# term_clock.net
KiCad netlist of a schematic drawn in EAGLE
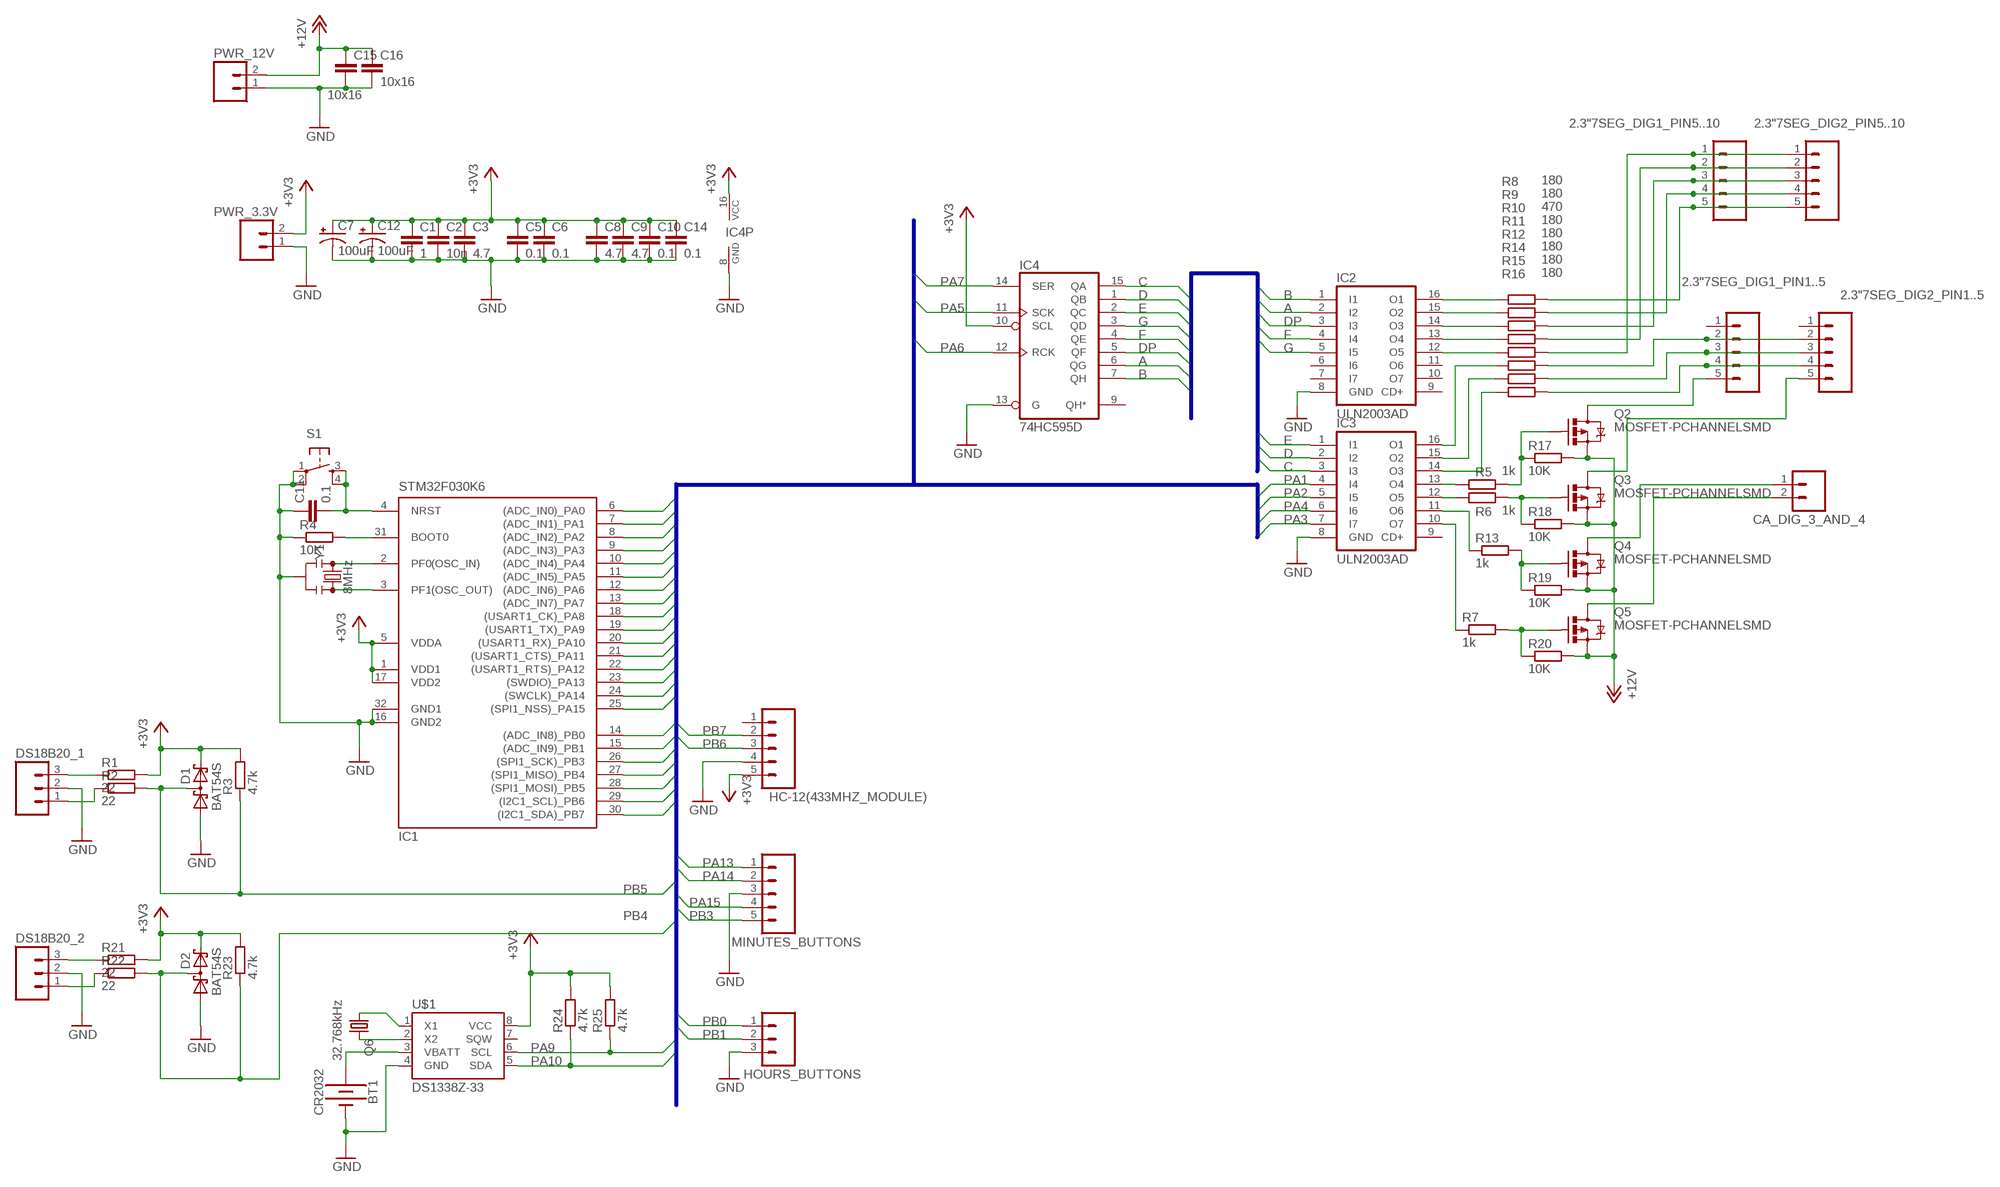
[diagram p0: schematic, sheet 1]

(export (version "E")
  (design (tool "Eeschema 10.0.6"))
  (components
    (comp (ref "2.3\"7SEG_DIG1_PIN1..5")
      (value "M05")
      (footprint "eagle-import:05P")
      (libsource (lib "eagle-import") (part "M05"))
    )
    (comp (ref "2.3\"7SEG_DIG1_PIN5..10")
      (value "M05")
      (footprint "eagle-import:05P")
      (libsource (lib "eagle-import") (part "M05"))
    )
    (comp (ref "2.3\"7SEG_DIG2_PIN1..5")
      (value "M05")
      (footprint "eagle-import:05P")
      (libsource (lib "eagle-import") (part "M05"))
    )
    (comp (ref "2.3\"7SEG_DIG2_PIN5..10")
      (value "M05")
      (footprint "eagle-import:05P")
      (libsource (lib "eagle-import") (part "M05"))
    )
    (comp (ref "BT1")
      (value "CR2032")
      (footprint "eagle-import:BATTCOM_20MM_PTH")
      (libsource (lib "eagle-import") (part "BATTERY-20MM_PTH"))
    )
    (comp (ref "C1")
      (value "1")
      (footprint "eagle-import:C0805")
      (libsource (lib "eagle-import") (part "C-EUC0805"))
    )
    (comp (ref "C2")
      (value "10n")
      (footprint "eagle-import:C0805")
      (libsource (lib "eagle-import") (part "C-EUC0805"))
    )
    (comp (ref "C3")
      (value "4.7")
      (footprint "eagle-import:C0805")
      (libsource (lib "eagle-import") (part "C-EUC0805"))
    )
    (comp (ref "C5")
      (value "0.1")
      (footprint "eagle-import:C0805")
      (libsource (lib "eagle-import") (part "C-EUC0805"))
    )
    (comp (ref "C6")
      (value "0.1")
      (footprint "eagle-import:C0805")
      (libsource (lib "eagle-import") (part "C-EUC0805"))
    )
    (comp (ref "C7")
      (value "100uF")
      (footprint "eagle-import:EIA7343")
      (libsource (lib "eagle-import") (part "100UF-POLAR-EIA7343-16V-10%(TANT)"))
    )
    (comp (ref "C8")
      (value "4.7")
      (footprint "eagle-import:C0805")
      (libsource (lib "eagle-import") (part "C-EUC0805"))
    )
    (comp (ref "C9")
      (value "4.7")
      (footprint "eagle-import:C0805")
      (libsource (lib "eagle-import") (part "C-EUC0805"))
    )
    (comp (ref "C10")
      (value "0.1")
      (footprint "eagle-import:C0805")
      (libsource (lib "eagle-import") (part "C-EUC0805"))
    )
    (comp (ref "C11")
      (value "0.1")
      (footprint "eagle-import:C0805")
      (libsource (lib "eagle-import") (part "C-EUC0805"))
    )
    (comp (ref "C12")
      (value "100uF")
      (footprint "eagle-import:EIA7343")
      (libsource (lib "eagle-import") (part "100UF-POLAR-EIA7343-16V-10%(TANT)"))
    )
    (comp (ref "C14")
      (value "0.1")
      (footprint "eagle-import:C0805")
      (libsource (lib "eagle-import") (part "C-EUC0805"))
    )
    (comp (ref "C15")
      (value "10x16")
      (footprint "eagle-import:C1206")
      (libsource (lib "eagle-import") (part "C-EUC1206"))
    )
    (comp (ref "C16")
      (value "10x16")
      (footprint "eagle-import:C1206")
      (libsource (lib "eagle-import") (part "C-EUC1206"))
    )
    (comp (ref "CA_DIG_3_AND_4")
      (value "M02")
      (footprint "eagle-import:02P")
      (libsource (lib "eagle-import") (part "M02"))
    )
    (comp (ref "D1")
      (value "BAT54S")
      (footprint "eagle-import:SOT23")
      (libsource (lib "eagle-import") (part "BAT54S"))
    )
    (comp (ref "D2")
      (value "BAT54S")
      (footprint "eagle-import:SOT23")
      (libsource (lib "eagle-import") (part "BAT54S"))
    )
    (comp (ref "DS18B20_1")
      (value "M03")
      (footprint "eagle-import:03P")
      (libsource (lib "eagle-import") (part "M03"))
    )
    (comp (ref "DS18B20_2")
      (value "M03")
      (footprint "eagle-import:03P")
      (libsource (lib "eagle-import") (part "M03"))
    )
    (comp (ref "HC-12(433MHZ_MODULE)")
      (value "M05")
      (footprint "eagle-import:05P")
      (libsource (lib "eagle-import") (part "M05"))
    )
    (comp (ref "HOURS_BUTTONS")
      (value "M03")
      (footprint "eagle-import:03P")
      (libsource (lib "eagle-import") (part "M03"))
    )
    (comp (ref "IC1")
      (value "STM32F030K6")
      (footprint "eagle-import:TQFP32-08")
      (libsource (lib "eagle-import") (part "STM32F030K6"))
    )
    (comp (ref "IC2")
      (value "ULN2003AD")
      (footprint "eagle-import:SO16")
      (libsource (lib "eagle-import") (part "ULN2003AD"))
    )
    (comp (ref "IC3")
      (value "ULN2003AD")
      (footprint "eagle-import:SO16")
      (libsource (lib "eagle-import") (part "ULN2003AD"))
    )
    (comp (ref "IC4")
      (value "74HC595D")
      (footprint "eagle-import:SO16")
      (libsource (lib "eagle-import") (part "74595DHC"))
    )
    (comp (ref "MINUTES_BUTTONS")
      (value "M05")
      (footprint "eagle-import:05P")
      (libsource (lib "eagle-import") (part "M05"))
    )
    (comp (ref "PWR_3.3V")
      (value "M02")
      (footprint "eagle-import:02P")
      (libsource (lib "eagle-import") (part "M02"))
    )
    (comp (ref "PWR_12V")
      (value "M02")
      (footprint "eagle-import:02P")
      (libsource (lib "eagle-import") (part "M02"))
    )
    (comp (ref "Q2")
      (value "MOSFET-PCHANNELSMD")
      (footprint "eagle-import:SOT23-3")
      (libsource (lib "eagle-import") (part "MOSFET-PCHANNELSMD"))
    )
    (comp (ref "Q3")
      (value "MOSFET-PCHANNELSMD")
      (footprint "eagle-import:SOT23-3")
      (libsource (lib "eagle-import") (part "MOSFET-PCHANNELSMD"))
    )
    (comp (ref "Q4")
      (value "MOSFET-PCHANNELSMD")
      (footprint "eagle-import:SOT23-3")
      (libsource (lib "eagle-import") (part "MOSFET-PCHANNELSMD"))
    )
    (comp (ref "Q5")
      (value "MOSFET-PCHANNELSMD")
      (footprint "eagle-import:SOT23-3")
      (libsource (lib "eagle-import") (part "MOSFET-PCHANNELSMD"))
    )
    (comp (ref "Q6")
      (value "32.768kHz")
      (footprint "eagle-import:TC38H")
      (libsource (lib "eagle-import") (part "CRYSTALTC38H"))
    )
    (comp (ref "R1")
      (value "22")
      (footprint "eagle-import:R0805")
      (libsource (lib "eagle-import") (part "R-EU_R0805"))
    )
    (comp (ref "R2")
      (value "22")
      (footprint "eagle-import:R0805")
      (libsource (lib "eagle-import") (part "R-EU_R0805"))
    )
    (comp (ref "R3")
      (value "4.7k")
      (footprint "eagle-import:R0805")
      (libsource (lib "eagle-import") (part "R-EU_R0805"))
    )
    (comp (ref "R4")
      (value "10K")
      (footprint "eagle-import:R0805")
      (libsource (lib "eagle-import") (part "R-EU_R0805"))
    )
    (comp (ref "R5")
      (value "1k")
      (footprint "eagle-import:R0603")
      (libsource (lib "eagle-import") (part "R-EU_R0603"))
    )
    (comp (ref "R6")
      (value "1k")
      (footprint "eagle-import:R0603")
      (libsource (lib "eagle-import") (part "R-EU_R0603"))
    )
    (comp (ref "R7")
      (value "1k")
      (footprint "eagle-import:R0603")
      (libsource (lib "eagle-import") (part "R-EU_R0603"))
    )
    (comp (ref "R8")
      (value "180")
      (footprint "eagle-import:R1206")
      (libsource (lib "eagle-import") (part "R-EU_R1206"))
    )
    (comp (ref "R9")
      (value "180")
      (footprint "eagle-import:R1206")
      (libsource (lib "eagle-import") (part "R-EU_R1206"))
    )
    (comp (ref "R10")
      (value "470")
      (footprint "eagle-import:R1206")
      (libsource (lib "eagle-import") (part "R-EU_R1206"))
    )
    (comp (ref "R11")
      (value "180")
      (footprint "eagle-import:R1206")
      (libsource (lib "eagle-import") (part "R-EU_R1206"))
    )
    (comp (ref "R12")
      (value "180")
      (footprint "eagle-import:R1206")
      (libsource (lib "eagle-import") (part "R-EU_R1206"))
    )
    (comp (ref "R13")
      (value "1k")
      (footprint "eagle-import:R0603")
      (libsource (lib "eagle-import") (part "R-EU_R0603"))
    )
    (comp (ref "R14")
      (value "180")
      (footprint "eagle-import:R1206")
      (libsource (lib "eagle-import") (part "R-EU_R1206"))
    )
    (comp (ref "R15")
      (value "180")
      (footprint "eagle-import:R1206")
      (libsource (lib "eagle-import") (part "R-EU_R1206"))
    )
    (comp (ref "R16")
      (value "180")
      (footprint "eagle-import:R1206")
      (libsource (lib "eagle-import") (part "R-EU_R1206"))
    )
    (comp (ref "R17")
      (value "10K")
      (footprint "eagle-import:R0603")
      (libsource (lib "eagle-import") (part "R-EU_R0603"))
    )
    (comp (ref "R18")
      (value "10K")
      (footprint "eagle-import:R0603")
      (libsource (lib "eagle-import") (part "R-EU_R0603"))
    )
    (comp (ref "R19")
      (value "10K")
      (footprint "eagle-import:R0603")
      (libsource (lib "eagle-import") (part "R-EU_R0603"))
    )
    (comp (ref "R20")
      (value "10K")
      (footprint "eagle-import:R0603")
      (libsource (lib "eagle-import") (part "R-EU_R0603"))
    )
    (comp (ref "R21")
      (value "22")
      (footprint "eagle-import:R0805")
      (libsource (lib "eagle-import") (part "R-EU_R0805"))
    )
    (comp (ref "R22")
      (value "22")
      (footprint "eagle-import:R0805")
      (libsource (lib "eagle-import") (part "R-EU_R0805"))
    )
    (comp (ref "R23")
      (value "4.7k")
      (footprint "eagle-import:R0805")
      (libsource (lib "eagle-import") (part "R-EU_R0805"))
    )
    (comp (ref "R24")
      (value "4.7k")
      (footprint "eagle-import:R0805")
      (libsource (lib "eagle-import") (part "R-EU_R0805"))
    )
    (comp (ref "R25")
      (value "4.7k")
      (footprint "eagle-import:R0805")
      (libsource (lib "eagle-import") (part "R-EU_R0805"))
    )
    (comp (ref "S1")
      (value "TAC_SWITCHSMD")
      (footprint "eagle-import:TACTILE_SWITCH_SMD")
      (libsource (lib "eagle-import") (part "TAC_SWITCHSMD"))
    )
    (comp (ref "U$1")
      (value "DS1338Z-33")
      (footprint "eagle-import:SO08")
      (libsource (lib "eagle-import") (part "DS1307SO8"))
    )
    (comp (ref "Y1")
      (value "8MHz")
      (footprint "eagle-import:RESONATOR-SMD-3.2X1.3")
      (libsource (lib "eagle-import") (part "RESONATOR-8MHZSMD_3.2X1.3"))
    )
  )
  (nets
    (net (code "1") (name "+3V3") (class "Default")
      (node (ref "C1") (pin "1") (pinfunction "1_1") (pintype "passive"))
      (node (ref "C10") (pin "1") (pinfunction "1_1") (pintype "passive"))
      (node (ref "C12") (pin "A") (pinfunction "+_A") (pintype "passive"))
      (node (ref "C14") (pin "1") (pinfunction "1_1") (pintype "passive"))
      (node (ref "C2") (pin "1") (pinfunction "1_1") (pintype "passive"))
      (node (ref "C3") (pin "1") (pinfunction "1_1") (pintype "passive"))
      (node (ref "C5") (pin "1") (pinfunction "1_1") (pintype "passive"))
      (node (ref "C6") (pin "1") (pinfunction "1_1") (pintype "passive"))
      (node (ref "C7") (pin "A") (pinfunction "+_A") (pintype "passive"))
      (node (ref "C8") (pin "1") (pinfunction "1_1") (pintype "passive"))
      (node (ref "C9") (pin "1") (pinfunction "1_1") (pintype "passive"))
      (node (ref "D1") (pin "2") (pinfunction "C2_2") (pintype "passive"))
      (node (ref "D2") (pin "2") (pinfunction "C2_2") (pintype "passive"))
      (node (ref "HC-12(433MHZ_MODULE)") (pin "5") (pinfunction "5_5") (pintype "passive"))
      (node (ref "IC1") (pin "1") (pinfunction "VDD1_1") (pintype "power_in"))
      (node (ref "IC1") (pin "17") (pinfunction "VDD2_17") (pintype "power_in"))
      (node (ref "IC1") (pin "5") (pinfunction "VDDA_5") (pintype "power_in"))
      (node (ref "IC4") (pin "10") (pinfunction "SCL_10") (pintype "input"))
      (node (ref "IC4") (pin "16") (pinfunction "VCC_16") (pintype "power_in"))
      (node (ref "PWR_3.3V") (pin "2") (pinfunction "2_2") (pintype "passive"))
      (node (ref "R1") (pin "2") (pinfunction "2_2") (pintype "passive"))
      (node (ref "R21") (pin "2") (pinfunction "2_2") (pintype "passive"))
      (node (ref "R23") (pin "2") (pinfunction "2_2") (pintype "passive"))
      (node (ref "R24") (pin "2") (pinfunction "2_2") (pintype "passive"))
      (node (ref "R25") (pin "2") (pinfunction "2_2") (pintype "passive"))
      (node (ref "R3") (pin "2") (pinfunction "2_2") (pintype "passive"))
      (node (ref "U$1") (pin "8") (pinfunction "VCC_8") (pintype "bidirectional"))
    )
    (net (code "2") (name "+12V") (class "Default")
      (node (ref "C15") (pin "1") (pinfunction "1_1") (pintype "passive"))
      (node (ref "C16") (pin "1") (pinfunction "1_1") (pintype "passive"))
      (node (ref "PWR_12V") (pin "2") (pinfunction "2_2") (pintype "passive"))
      (node (ref "Q2") (pin "2") (pinfunction "S_2") (pintype "passive"))
      (node (ref "Q3") (pin "2") (pinfunction "S_2") (pintype "passive"))
      (node (ref "Q4") (pin "2") (pinfunction "S_2") (pintype "passive"))
      (node (ref "Q5") (pin "2") (pinfunction "S_2") (pintype "passive"))
      (node (ref "R17") (pin "2") (pinfunction "2_2") (pintype "passive"))
      (node (ref "R18") (pin "2") (pinfunction "2_2") (pintype "passive"))
      (node (ref "R19") (pin "2") (pinfunction "2_2") (pintype "passive"))
      (node (ref "R20") (pin "2") (pinfunction "2_2") (pintype "passive"))
    )
    (net (code "3") (name "/A") (class "Default")
      (node (ref "IC2") (pin "2") (pinfunction "I2_2") (pintype "input"))
      (node (ref "IC4") (pin "6") (pinfunction "QG_6") (pintype "tri_state"))
    )
    (net (code "4") (name "/B") (class "Default")
      (node (ref "IC2") (pin "1") (pinfunction "I1_1") (pintype "input"))
      (node (ref "IC4") (pin "7") (pinfunction "QH_7") (pintype "tri_state"))
    )
    (net (code "5") (name "/C") (class "Default")
      (node (ref "IC3") (pin "3") (pinfunction "I3_3") (pintype "input"))
      (node (ref "IC4") (pin "15") (pinfunction "QA_15") (pintype "tri_state"))
    )
    (net (code "6") (name "/D") (class "Default")
      (node (ref "IC3") (pin "2") (pinfunction "I2_2") (pintype "input"))
      (node (ref "IC4") (pin "1") (pinfunction "QB_1") (pintype "tri_state"))
    )
    (net (code "7") (name "/DP") (class "Default")
      (node (ref "IC2") (pin "3") (pinfunction "I3_3") (pintype "input"))
      (node (ref "IC4") (pin "5") (pinfunction "QF_5") (pintype "tri_state"))
    )
    (net (code "8") (name "/E") (class "Default")
      (node (ref "IC3") (pin "1") (pinfunction "I1_1") (pintype "input"))
      (node (ref "IC4") (pin "2") (pinfunction "QC_2") (pintype "tri_state"))
    )
    (net (code "9") (name "/F") (class "Default")
      (node (ref "IC2") (pin "4") (pinfunction "I4_4") (pintype "input"))
      (node (ref "IC4") (pin "4") (pinfunction "QE_4") (pintype "tri_state"))
    )
    (net (code "10") (name "/G") (class "Default")
      (node (ref "IC2") (pin "5") (pinfunction "I5_5") (pintype "input"))
      (node (ref "IC4") (pin "3") (pinfunction "QD_3") (pintype "tri_state"))
    )
    (net (code "11") (name "/PA1") (class "Default")
      (node (ref "IC1") (pin "7") (pinfunction "(ADC_IN1)_PA1_7") (pintype "bidirectional"))
      (node (ref "IC3") (pin "4") (pinfunction "I4_4") (pintype "input"))
    )
    (net (code "12") (name "/PA2") (class "Default")
      (node (ref "IC1") (pin "8") (pinfunction "(ADC_IN2)_PA2_8") (pintype "bidirectional"))
      (node (ref "IC3") (pin "5") (pinfunction "I5_5") (pintype "input"))
    )
    (net (code "13") (name "/PA3") (class "Default")
      (node (ref "IC1") (pin "9") (pinfunction "(ADC_IN3)_PA3_9") (pintype "bidirectional"))
      (node (ref "IC3") (pin "7") (pinfunction "I7_7") (pintype "input"))
    )
    (net (code "14") (name "/PA4") (class "Default")
      (node (ref "IC1") (pin "10") (pinfunction "(ADC_IN4)_PA4_10") (pintype "bidirectional"))
      (node (ref "IC3") (pin "6") (pinfunction "I6_6") (pintype "input"))
    )
    (net (code "15") (name "/PA5") (class "Default")
      (node (ref "IC1") (pin "11") (pinfunction "(ADC_IN5)_PA5_11") (pintype "bidirectional"))
      (node (ref "IC4") (pin "11") (pinfunction "SCK_11") (pintype "input"))
    )
    (net (code "16") (name "/PA6") (class "Default")
      (node (ref "IC1") (pin "12") (pinfunction "(ADC_IN6)_PA6_12") (pintype "bidirectional"))
      (node (ref "IC4") (pin "12") (pinfunction "RCK_12") (pintype "input"))
    )
    (net (code "17") (name "/PA7") (class "Default")
      (node (ref "IC1") (pin "13") (pinfunction "(ADC_IN7)_PA7_13") (pintype "bidirectional"))
      (node (ref "IC4") (pin "14") (pinfunction "SER_14") (pintype "input"))
    )
    (net (code "18") (name "/PA9") (class "Default")
      (node (ref "IC1") (pin "19") (pinfunction "(USART1_TX)_PA9_19") (pintype "bidirectional"))
      (node (ref "R25") (pin "1") (pinfunction "1_1") (pintype "passive"))
      (node (ref "U$1") (pin "6") (pinfunction "SCL_6") (pintype "bidirectional"))
    )
    (net (code "19") (name "/PA10") (class "Default")
      (node (ref "IC1") (pin "20") (pinfunction "(USART1_RX)_PA10_20") (pintype "bidirectional"))
      (node (ref "R24") (pin "1") (pinfunction "1_1") (pintype "passive"))
      (node (ref "U$1") (pin "5") (pinfunction "SDA_5") (pintype "bidirectional"))
    )
    (net (code "20") (name "/PA13") (class "Default")
      (node (ref "IC1") (pin "23") (pinfunction "(SWDIO)_PA13_23") (pintype "bidirectional"))
      (node (ref "MINUTES_BUTTONS") (pin "1") (pinfunction "1_1") (pintype "passive"))
    )
    (net (code "21") (name "/PA14") (class "Default")
      (node (ref "IC1") (pin "24") (pinfunction "(SWCLK)_PA14_24") (pintype "bidirectional"))
      (node (ref "MINUTES_BUTTONS") (pin "2") (pinfunction "2_2") (pintype "passive"))
    )
    (net (code "22") (name "/PA15") (class "Default")
      (node (ref "IC1") (pin "25") (pinfunction "(SPI1_NSS)_PA15_25") (pintype "bidirectional"))
      (node (ref "MINUTES_BUTTONS") (pin "4") (pinfunction "4_4") (pintype "passive"))
    )
    (net (code "23") (name "/PB0") (class "Default")
      (node (ref "HOURS_BUTTONS") (pin "1") (pinfunction "1_1") (pintype "passive"))
      (node (ref "IC1") (pin "14") (pinfunction "(ADC_IN8)_PB0_14") (pintype "bidirectional"))
    )
    (net (code "24") (name "/PB1") (class "Default")
      (node (ref "HOURS_BUTTONS") (pin "2") (pinfunction "2_2") (pintype "passive"))
      (node (ref "IC1") (pin "15") (pinfunction "(ADC_IN9)_PB1_15") (pintype "bidirectional"))
    )
    (net (code "25") (name "/PB3") (class "Default")
      (node (ref "IC1") (pin "26") (pinfunction "(SPI1_SCK)_PB3_26") (pintype "bidirectional"))
      (node (ref "MINUTES_BUTTONS") (pin "5") (pinfunction "5_5") (pintype "passive"))
    )
    (net (code "26") (name "/PB4") (class "Default")
      (node (ref "D2") (pin "3") (pinfunction "C1A2_3") (pintype "passive"))
      (node (ref "IC1") (pin "27") (pinfunction "(SPI1_MISO)_PB4_27") (pintype "bidirectional"))
      (node (ref "R22") (pin "2") (pinfunction "2_2") (pintype "passive"))
      (node (ref "R23") (pin "1") (pinfunction "1_1") (pintype "passive"))
    )
    (net (code "27") (name "/PB5") (class "Default")
      (node (ref "D1") (pin "3") (pinfunction "C1A2_3") (pintype "passive"))
      (node (ref "IC1") (pin "28") (pinfunction "(SPI1_MOSI)_PB5_28") (pintype "bidirectional"))
      (node (ref "R2") (pin "2") (pinfunction "2_2") (pintype "passive"))
      (node (ref "R3") (pin "1") (pinfunction "1_1") (pintype "passive"))
    )
    (net (code "28") (name "/PB6") (class "Default")
      (node (ref "HC-12(433MHZ_MODULE)") (pin "3") (pinfunction "3_3") (pintype "passive"))
      (node (ref "IC1") (pin "29") (pinfunction "(I2C1_SCL)_PB6_29") (pintype "bidirectional"))
    )
    (net (code "29") (name "/PB7") (class "Default")
      (node (ref "HC-12(433MHZ_MODULE)") (pin "2") (pinfunction "2_2") (pintype "passive"))
      (node (ref "IC1") (pin "30") (pinfunction "(I2C1_SDA)_PB7_30") (pintype "bidirectional"))
    )
    (net (code "30") (name "GND") (class "Default")
      (node (ref "BT1") (pin "2") (pinfunction "-_2") (pintype "power_in"))
      (node (ref "C1") (pin "2") (pinfunction "2_2") (pintype "passive"))
      (node (ref "C10") (pin "2") (pinfunction "2_2") (pintype "passive"))
      (node (ref "C11") (pin "1") (pinfunction "1_1") (pintype "passive"))
      (node (ref "C12") (pin "C") (pinfunction "-_C") (pintype "passive"))
      (node (ref "C14") (pin "2") (pinfunction "2_2") (pintype "passive"))
      (node (ref "C15") (pin "2") (pinfunction "2_2") (pintype "passive"))
      (node (ref "C16") (pin "2") (pinfunction "2_2") (pintype "passive"))
      (node (ref "C2") (pin "2") (pinfunction "2_2") (pintype "passive"))
      (node (ref "C3") (pin "2") (pinfunction "2_2") (pintype "passive"))
      (node (ref "C5") (pin "2") (pinfunction "2_2") (pintype "passive"))
      (node (ref "C6") (pin "2") (pinfunction "2_2") (pintype "passive"))
      (node (ref "C7") (pin "C") (pinfunction "-_C") (pintype "passive"))
      (node (ref "C8") (pin "2") (pinfunction "2_2") (pintype "passive"))
      (node (ref "C9") (pin "2") (pinfunction "2_2") (pintype "passive"))
      (node (ref "D1") (pin "1") (pinfunction "A1_1") (pintype "passive"))
      (node (ref "D2") (pin "1") (pinfunction "A1_1") (pintype "passive"))
      (node (ref "DS18B20_1") (pin "2") (pinfunction "2_2") (pintype "passive"))
      (node (ref "DS18B20_2") (pin "2") (pinfunction "2_2") (pintype "passive"))
      (node (ref "HC-12(433MHZ_MODULE)") (pin "4") (pinfunction "4_4") (pintype "passive"))
      (node (ref "HOURS_BUTTONS") (pin "3") (pinfunction "3_3") (pintype "passive"))
      (node (ref "IC1") (pin "16") (pinfunction "GND2_16") (pintype "power_in"))
      (node (ref "IC1") (pin "32") (pinfunction "GND1_32") (pintype "power_in"))
      (node (ref "IC2") (pin "8") (pinfunction "GND_8") (pintype "power_in"))
      (node (ref "IC3") (pin "8") (pinfunction "GND_8") (pintype "power_in"))
      (node (ref "IC4") (pin "13") (pinfunction "G_13") (pintype "input"))
      (node (ref "IC4") (pin "8") (pinfunction "GND_8") (pintype "power_in"))
      (node (ref "MINUTES_BUTTONS") (pin "3") (pinfunction "3_3") (pintype "passive"))
      (node (ref "PWR_12V") (pin "1") (pinfunction "1_1") (pintype "passive"))
      (node (ref "PWR_3.3V") (pin "1") (pinfunction "1_1") (pintype "passive"))
      (node (ref "R4") (pin "1") (pinfunction "1_1") (pintype "passive"))
      (node (ref "S1") (pin "1") (pinfunction "1_1") (pintype "passive"))
      (node (ref "S1") (pin "2") (pinfunction "2_2") (pintype "passive"))
      (node (ref "U$1") (pin "4") (pinfunction "GND_4") (pintype "bidirectional"))
      (node (ref "Y1") (pin "2") (pinfunction "2_2") (pintype "passive"))
    )
    (net (code "31") (name "Net-(2.3\"7SEG_DIG1_PIN1..5-Pad2)") (class "Default")
      (node (ref "2.3\"7SEG_DIG1_PIN1..5") (pin "2") (pinfunction "2_2") (pintype "passive"))
      (node (ref "2.3\"7SEG_DIG2_PIN1..5") (pin "2") (pinfunction "2_2") (pintype "passive"))
      (node (ref "R14") (pin "2") (pinfunction "2_2") (pintype "passive"))
    )
    (net (code "32") (name "Net-(2.3\"7SEG_DIG1_PIN1..5-Pad3)") (class "Default")
      (node (ref "2.3\"7SEG_DIG1_PIN1..5") (pin "3") (pinfunction "3_3") (pintype "passive"))
      (node (ref "2.3\"7SEG_DIG2_PIN1..5") (pin "3") (pinfunction "3_3") (pintype "passive"))
      (node (ref "R15") (pin "2") (pinfunction "2_2") (pintype "passive"))
    )
    (net (code "33") (name "Net-(2.3\"7SEG_DIG1_PIN1..5-Pad4)") (class "Default")
      (node (ref "2.3\"7SEG_DIG1_PIN1..5") (pin "4") (pinfunction "4_4") (pintype "passive"))
      (node (ref "2.3\"7SEG_DIG2_PIN1..5") (pin "4") (pinfunction "4_4") (pintype "passive"))
      (node (ref "R16") (pin "2") (pinfunction "2_2") (pintype "passive"))
    )
    (net (code "34") (name "Net-(2.3\"7SEG_DIG1_PIN5..10-Pad1)") (class "Default")
      (node (ref "2.3\"7SEG_DIG1_PIN5..10") (pin "1") (pinfunction "1_1") (pintype "passive"))
      (node (ref "2.3\"7SEG_DIG2_PIN5..10") (pin "1") (pinfunction "1_1") (pintype "passive"))
      (node (ref "R12") (pin "2") (pinfunction "2_2") (pintype "passive"))
    )
    (net (code "35") (name "Net-(2.3\"7SEG_DIG1_PIN5..10-Pad2)") (class "Default")
      (node (ref "2.3\"7SEG_DIG1_PIN5..10") (pin "2") (pinfunction "2_2") (pintype "passive"))
      (node (ref "2.3\"7SEG_DIG2_PIN5..10") (pin "2") (pinfunction "2_2") (pintype "passive"))
      (node (ref "R11") (pin "2") (pinfunction "2_2") (pintype "passive"))
    )
    (net (code "36") (name "Net-(2.3\"7SEG_DIG1_PIN5..10-Pad3)") (class "Default")
      (node (ref "2.3\"7SEG_DIG1_PIN5..10") (pin "3") (pinfunction "3_3") (pintype "passive"))
      (node (ref "2.3\"7SEG_DIG2_PIN5..10") (pin "3") (pinfunction "3_3") (pintype "passive"))
      (node (ref "R10") (pin "2") (pinfunction "2_2") (pintype "passive"))
    )
    (net (code "37") (name "Net-(2.3\"7SEG_DIG1_PIN5..10-Pad4)") (class "Default")
      (node (ref "2.3\"7SEG_DIG1_PIN5..10") (pin "4") (pinfunction "4_4") (pintype "passive"))
      (node (ref "2.3\"7SEG_DIG2_PIN5..10") (pin "4") (pinfunction "4_4") (pintype "passive"))
      (node (ref "R9") (pin "2") (pinfunction "2_2") (pintype "passive"))
    )
    (net (code "38") (name "Net-(2.3\"7SEG_DIG1_PIN5..10-Pad5)") (class "Default")
      (node (ref "2.3\"7SEG_DIG1_PIN5..10") (pin "5") (pinfunction "5_5") (pintype "passive"))
      (node (ref "2.3\"7SEG_DIG2_PIN5..10") (pin "5") (pinfunction "5_5") (pintype "passive"))
      (node (ref "R8") (pin "2") (pinfunction "2_2") (pintype "passive"))
    )
    (net (code "39") (name "Net-(BT1-+)") (class "Default")
      (node (ref "BT1") (pin "1") (pinfunction "+_1") (pintype "power_in"))
      (node (ref "U$1") (pin "3") (pinfunction "VBATT_3") (pintype "bidirectional"))
    )
    (net (code "40") (name "Net-(DS18B20_1-Pad1)") (class "Default")
      (node (ref "DS18B20_1") (pin "1") (pinfunction "1_1") (pintype "passive"))
      (node (ref "R2") (pin "1") (pinfunction "1_1") (pintype "passive"))
    )
    (net (code "41") (name "Net-(DS18B20_1-Pad3)") (class "Default")
      (node (ref "DS18B20_1") (pin "3") (pinfunction "3_3") (pintype "passive"))
      (node (ref "R1") (pin "1") (pinfunction "1_1") (pintype "passive"))
    )
    (net (code "42") (name "Net-(DS18B20_2-Pad1)") (class "Default")
      (node (ref "DS18B20_2") (pin "1") (pinfunction "1_1") (pintype "passive"))
      (node (ref "R22") (pin "1") (pinfunction "1_1") (pintype "passive"))
    )
    (net (code "43") (name "Net-(DS18B20_2-Pad3)") (class "Default")
      (node (ref "DS18B20_2") (pin "3") (pinfunction "3_3") (pintype "passive"))
      (node (ref "R21") (pin "1") (pinfunction "1_1") (pintype "passive"))
    )
    (net (code "44") (name "Net-(IC1-BOOT0)") (class "Default")
      (node (ref "IC1") (pin "31") (pinfunction "BOOT0_31") (pintype "passive"))
      (node (ref "R4") (pin "2") (pinfunction "2_2") (pintype "passive"))
    )
    (net (code "45") (name "Net-(IC1-NRST)") (class "Default")
      (node (ref "C11") (pin "2") (pinfunction "2_2") (pintype "passive"))
      (node (ref "IC1") (pin "4") (pinfunction "NRST_4") (pintype "input"))
      (node (ref "S1") (pin "3") (pinfunction "3_3") (pintype "passive"))
      (node (ref "S1") (pin "4") (pinfunction "4_4") (pintype "passive"))
    )
    (net (code "46") (name "Net-(IC1-PF0(OSC_IN))") (class "Default")
      (node (ref "IC1") (pin "2") (pinfunction "PF0(OSC_IN)_2") (pintype "bidirectional"))
      (node (ref "Y1") (pin "1") (pinfunction "1_1") (pintype "passive"))
    )
    (net (code "47") (name "Net-(IC1-PF1(OSC_OUT))") (class "Default")
      (node (ref "IC1") (pin "3") (pinfunction "PF1(OSC_OUT)_3") (pintype "bidirectional"))
      (node (ref "Y1") (pin "3") (pinfunction "3_3") (pintype "passive"))
    )
    (net (code "48") (name "Net-(IC2-O1)") (class "Default")
      (node (ref "IC2") (pin "16") (pinfunction "O1_16") (pintype "open_collector"))
      (node (ref "R8") (pin "1") (pinfunction "1_1") (pintype "passive"))
    )
    (net (code "49") (name "Net-(IC2-O2)") (class "Default")
      (node (ref "IC2") (pin "15") (pinfunction "O2_15") (pintype "open_collector"))
      (node (ref "R9") (pin "1") (pinfunction "1_1") (pintype "passive"))
    )
    (net (code "50") (name "Net-(IC2-O3)") (class "Default")
      (node (ref "IC2") (pin "14") (pinfunction "O3_14") (pintype "open_collector"))
      (node (ref "R10") (pin "1") (pinfunction "1_1") (pintype "passive"))
    )
    (net (code "51") (name "Net-(IC2-O4)") (class "Default")
      (node (ref "IC2") (pin "13") (pinfunction "O4_13") (pintype "open_collector"))
      (node (ref "R11") (pin "1") (pinfunction "1_1") (pintype "passive"))
    )
    (net (code "52") (name "Net-(IC2-O5)") (class "Default")
      (node (ref "IC2") (pin "12") (pinfunction "O5_12") (pintype "open_collector"))
      (node (ref "R12") (pin "1") (pinfunction "1_1") (pintype "passive"))
    )
    (net (code "53") (name "Net-(IC3-O1)") (class "Default")
      (node (ref "IC3") (pin "16") (pinfunction "O1_16") (pintype "open_collector"))
      (node (ref "R14") (pin "1") (pinfunction "1_1") (pintype "passive"))
    )
    (net (code "54") (name "Net-(IC3-O2)") (class "Default")
      (node (ref "IC3") (pin "15") (pinfunction "O2_15") (pintype "open_collector"))
      (node (ref "R15") (pin "1") (pinfunction "1_1") (pintype "passive"))
    )
    (net (code "55") (name "Net-(IC3-O3)") (class "Default")
      (node (ref "IC3") (pin "14") (pinfunction "O3_14") (pintype "open_collector"))
      (node (ref "R16") (pin "1") (pinfunction "1_1") (pintype "passive"))
    )
    (net (code "56") (name "Net-(IC3-O4)") (class "Default")
      (node (ref "IC3") (pin "13") (pinfunction "O4_13") (pintype "open_collector"))
      (node (ref "R5") (pin "1") (pinfunction "1_1") (pintype "passive"))
    )
    (net (code "57") (name "Net-(IC3-O5)") (class "Default")
      (node (ref "IC3") (pin "12") (pinfunction "O5_12") (pintype "open_collector"))
      (node (ref "R6") (pin "1") (pinfunction "1_1") (pintype "passive"))
    )
    (net (code "58") (name "Net-(IC3-O6)") (class "Default")
      (node (ref "IC3") (pin "11") (pinfunction "O6_11") (pintype "open_collector"))
      (node (ref "R13") (pin "1") (pinfunction "1_1") (pintype "passive"))
    )
    (net (code "59") (name "Net-(IC3-O7)") (class "Default")
      (node (ref "IC3") (pin "10") (pinfunction "O7_10") (pintype "open_collector"))
      (node (ref "R7") (pin "1") (pinfunction "1_1") (pintype "passive"))
    )
    (net (code "60") (name "Net-(Q2-D)") (class "Default")
      (node (ref "2.3\"7SEG_DIG1_PIN1..5") (pin "5") (pinfunction "5_5") (pintype "passive"))
      (node (ref "Q2") (pin "3") (pinfunction "D_3") (pintype "passive"))
    )
    (net (code "61") (name "Net-(Q2-G)") (class "Default")
      (node (ref "Q2") (pin "1") (pinfunction "G_1") (pintype "passive"))
      (node (ref "R17") (pin "1") (pinfunction "1_1") (pintype "passive"))
      (node (ref "R5") (pin "2") (pinfunction "2_2") (pintype "passive"))
    )
    (net (code "62") (name "Net-(Q3-D)") (class "Default")
      (node (ref "2.3\"7SEG_DIG2_PIN1..5") (pin "5") (pinfunction "5_5") (pintype "passive"))
      (node (ref "Q3") (pin "3") (pinfunction "D_3") (pintype "passive"))
    )
    (net (code "63") (name "Net-(Q3-G)") (class "Default")
      (node (ref "Q3") (pin "1") (pinfunction "G_1") (pintype "passive"))
      (node (ref "R18") (pin "1") (pinfunction "1_1") (pintype "passive"))
      (node (ref "R6") (pin "2") (pinfunction "2_2") (pintype "passive"))
    )
    (net (code "64") (name "Net-(Q4-D)") (class "Default")
      (node (ref "CA_DIG_3_AND_4") (pin "1") (pinfunction "1_1") (pintype "passive"))
      (node (ref "Q4") (pin "3") (pinfunction "D_3") (pintype "passive"))
    )
    (net (code "65") (name "Net-(Q4-G)") (class "Default")
      (node (ref "Q4") (pin "1") (pinfunction "G_1") (pintype "passive"))
      (node (ref "R13") (pin "2") (pinfunction "2_2") (pintype "passive"))
      (node (ref "R19") (pin "1") (pinfunction "1_1") (pintype "passive"))
    )
    (net (code "66") (name "Net-(Q5-D)") (class "Default")
      (node (ref "CA_DIG_3_AND_4") (pin "2") (pinfunction "2_2") (pintype "passive"))
      (node (ref "Q5") (pin "3") (pinfunction "D_3") (pintype "passive"))
    )
    (net (code "67") (name "Net-(Q5-G)") (class "Default")
      (node (ref "Q5") (pin "1") (pinfunction "G_1") (pintype "passive"))
      (node (ref "R20") (pin "1") (pinfunction "1_1") (pintype "passive"))
      (node (ref "R7") (pin "2") (pinfunction "2_2") (pintype "passive"))
    )
    (net (code "68") (name "Net-(U$1-X1)") (class "Default")
      (node (ref "Q6") (pin "1") (pinfunction "1_1") (pintype "passive"))
      (node (ref "U$1") (pin "1") (pinfunction "X1_1") (pintype "bidirectional"))
    )
    (net (code "69") (name "Net-(U$1-X2)") (class "Default")
      (node (ref "Q6") (pin "2") (pinfunction "2_2") (pintype "passive"))
      (node (ref "U$1") (pin "2") (pinfunction "X2_2") (pintype "bidirectional"))
    )
    (net (code "70") (name "unconnected-(2.3\"7SEG_DIG1_PIN1..5-Pad1)") (class "Default")
      (node (ref "2.3\"7SEG_DIG1_PIN1..5") (pin "1") (pinfunction "1_1") (pintype "passive"))
    )
    (net (code "71") (name "unconnected-(2.3\"7SEG_DIG2_PIN1..5-Pad1)") (class "Default")
      (node (ref "2.3\"7SEG_DIG2_PIN1..5") (pin "1") (pinfunction "1_1") (pintype "passive"))
    )
    (net (code "72") (name "unconnected-(HC-12(433MHZ_MODULE)-Pad1)") (class "Default")
      (node (ref "HC-12(433MHZ_MODULE)") (pin "1") (pinfunction "1_1") (pintype "passive"))
    )
    (net (code "73") (name "unconnected-(IC1-(ADC_IN0)_PA0-Pad6)") (class "Default")
      (node (ref "IC1") (pin "6") (pinfunction "(ADC_IN0)_PA0_6") (pintype "bidirectional"))
    )
    (net (code "74") (name "unconnected-(IC1-(USART1_CK)_PA8-Pad18)") (class "Default")
      (node (ref "IC1") (pin "18") (pinfunction "(USART1_CK)_PA8_18") (pintype "bidirectional"))
    )
    (net (code "75") (name "unconnected-(IC1-(USART1_CTS)_PA11-Pad21)") (class "Default")
      (node (ref "IC1") (pin "21") (pinfunction "(USART1_CTS)_PA11_21") (pintype "bidirectional"))
    )
    (net (code "76") (name "unconnected-(IC1-(USART1_RTS)_PA12-Pad22)") (class "Default")
      (node (ref "IC1") (pin "22") (pinfunction "(USART1_RTS)_PA12_22") (pintype "bidirectional"))
    )
    (net (code "77") (name "unconnected-(IC2-CD+-Pad9)") (class "Default")
      (node (ref "IC2") (pin "9") (pinfunction "CD+_9") (pintype "passive"))
    )
    (net (code "78") (name "unconnected-(IC2-I6-Pad6)") (class "Default")
      (node (ref "IC2") (pin "6") (pinfunction "I6_6") (pintype "input"))
    )
    (net (code "79") (name "unconnected-(IC2-I7-Pad7)") (class "Default")
      (node (ref "IC2") (pin "7") (pinfunction "I7_7") (pintype "input"))
    )
    (net (code "80") (name "unconnected-(IC2-O6-Pad11)") (class "Default")
      (node (ref "IC2") (pin "11") (pinfunction "O6_11") (pintype "open_collector"))
    )
    (net (code "81") (name "unconnected-(IC2-O7-Pad10)") (class "Default")
      (node (ref "IC2") (pin "10") (pinfunction "O7_10") (pintype "open_collector"))
    )
    (net (code "82") (name "unconnected-(IC3-CD+-Pad9)") (class "Default")
      (node (ref "IC3") (pin "9") (pinfunction "CD+_9") (pintype "passive"))
    )
    (net (code "83") (name "unconnected-(IC4A-QH*-Pad9)") (class "Default")
      (node (ref "IC4") (pin "9") (pinfunction "QH*_9") (pintype "tri_state"))
    )
    (net (code "84") (name "unconnected-(U$1-SQW-Pad7)") (class "Default")
      (node (ref "U$1") (pin "7") (pinfunction "SQW_7") (pintype "bidirectional"))
    )
  )
)
